# Register.net
KiCad netlist of a schematic drawn in Altium Designer
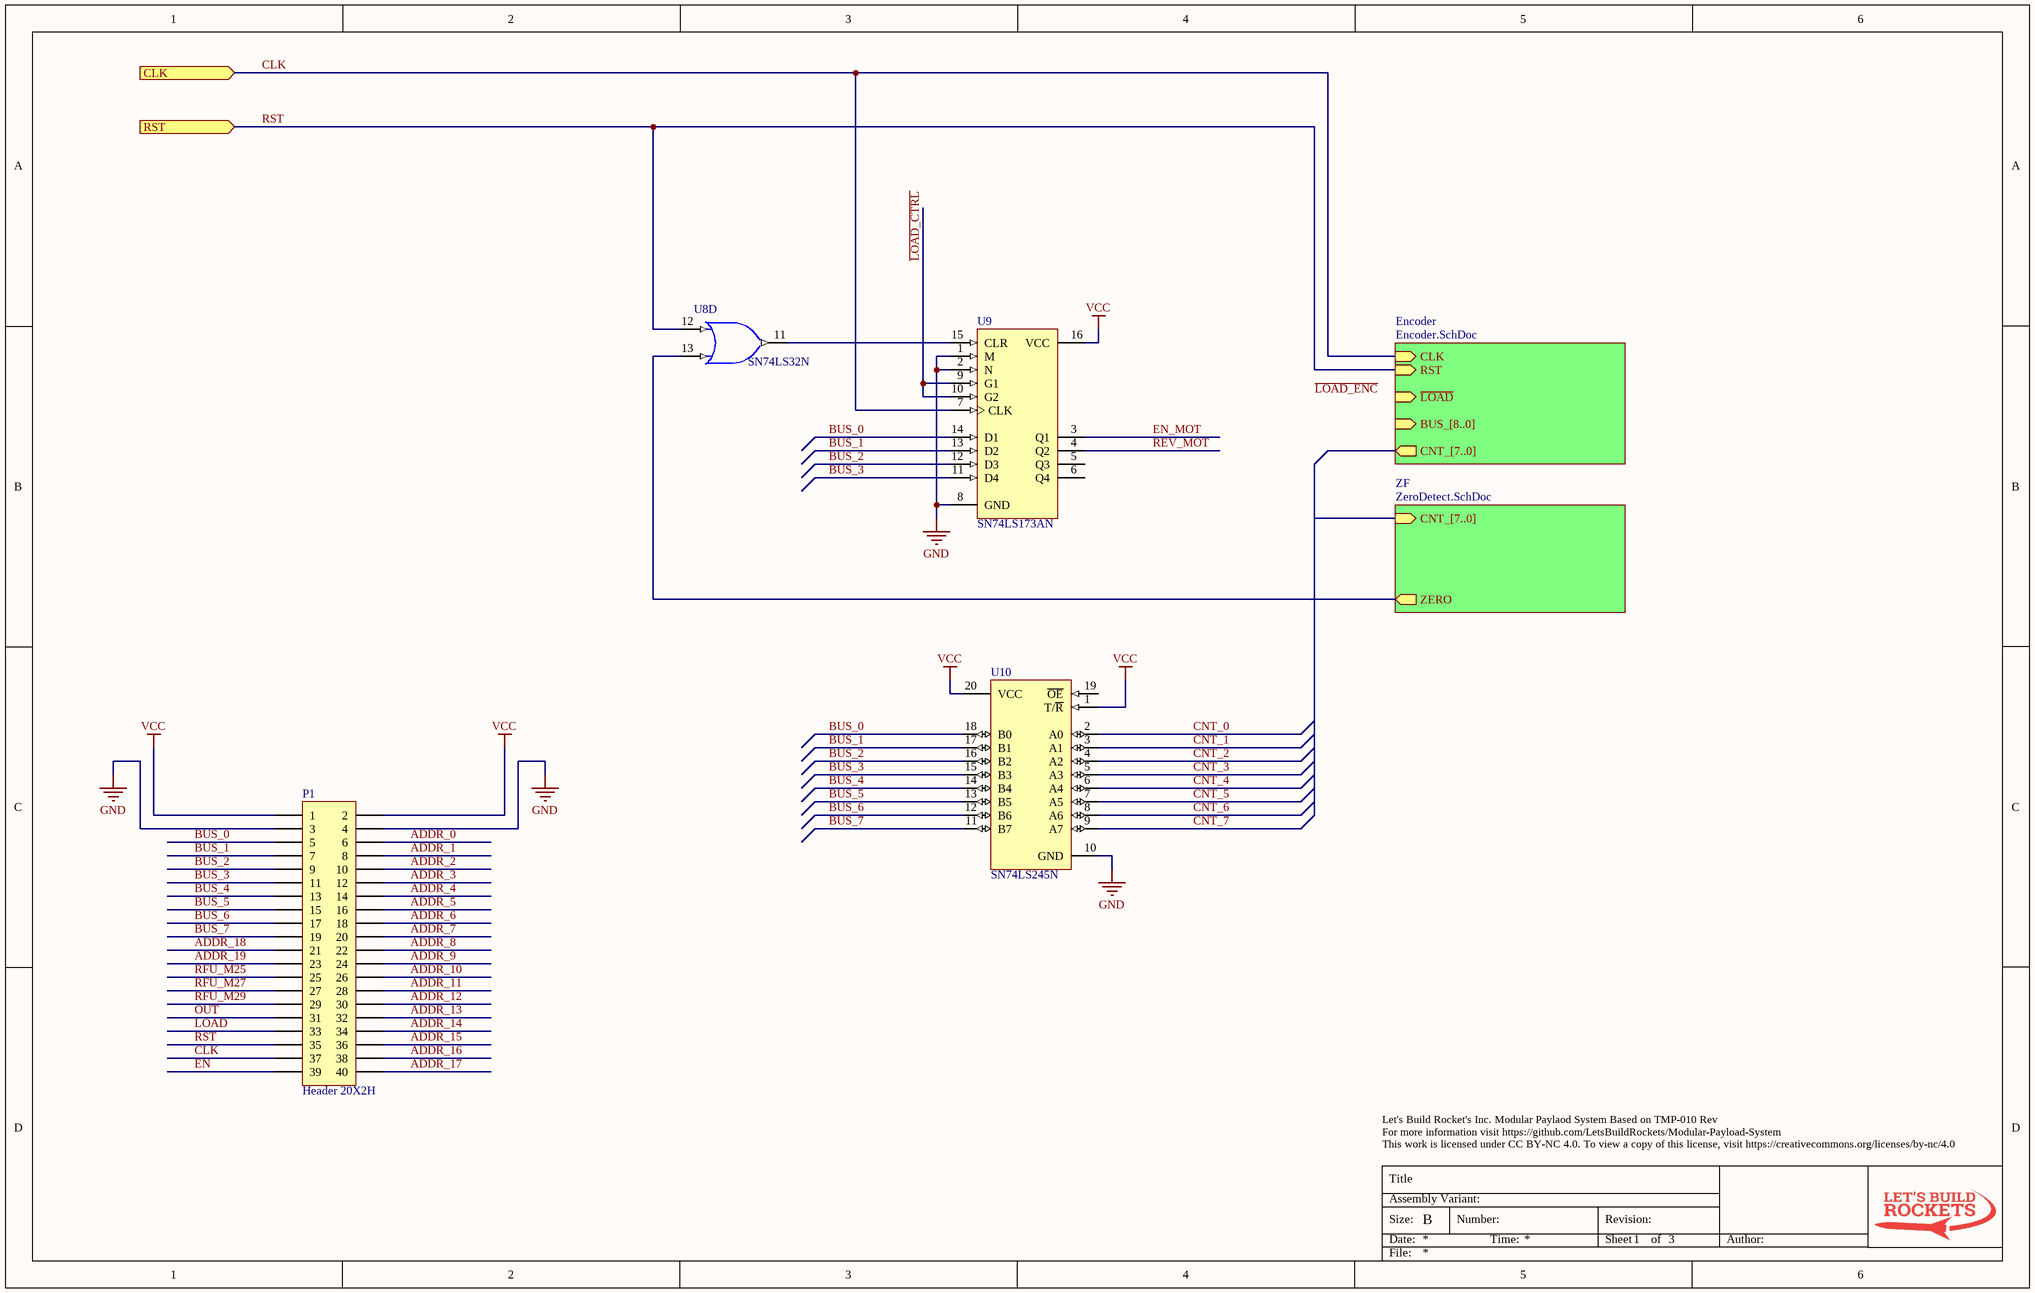
[diagram p0: Register.SchDoc]

(export (version "E")
  (design (tool "Eeschema 10.0.6"))
  (components
    (comp (ref "P1")
      (value "Header 20X2H")
      (footprint "HDR2X20H")
      (description "Header, 20-Pin, Dual row, Right Angle")
      (fields (field (name "PUBLISHER") "Altium Limited"))
      (libsource (lib "Miscellaneous Connectors") (part "Header 20X2H"))
    )
    (comp (ref "U8")
      (value "SN74LS32N")
      (footprint "N014")
      (description "Quadruple 2-Input Positive-OR Gate")
      (fields (field (name "PUBLISHER") "Altium Limited"))
      (libsource (lib "TI Logic Gate 2") (part "SN74LS32N"))
    )
    (comp (ref "U9")
      (value "SN74LS173AN")
      (footprint "N016D")
      (description "4-Bit D-Type Register with 3-State Outputs")
      (fields (field (name "PUBLISHER") "Altium Limited"))
      (libsource (lib "TI Logic Flip-Flop") (part "SN74LS173AN"))
    )
    (comp (ref "U10")
      (value "SN74LS245N")
      (footprint "N020")
      (description "Octal Bus Transceiver with 3-State Outputs")
      (fields (field (name "PUBLISHER") "Altium Limited"))
      (libsource (lib "TI Interface 8-Bit Line Transceiver") (part "SN74LS245N"))
    )
  )
  (nets
    (net (code "1") (name "/ADDR_0") (class "Default")
      (node (ref "P1") (pin "6") (pinfunction "6_6") (pintype "passive"))
    )
    (net (code "2") (name "/ADDR_1") (class "Default")
      (node (ref "P1") (pin "8") (pinfunction "8_8") (pintype "passive"))
    )
    (net (code "3") (name "/ADDR_2") (class "Default")
      (node (ref "P1") (pin "10") (pinfunction "10_10") (pintype "passive"))
    )
    (net (code "4") (name "/ADDR_3") (class "Default")
      (node (ref "P1") (pin "12") (pinfunction "12_12") (pintype "passive"))
    )
    (net (code "5") (name "/ADDR_4") (class "Default")
      (node (ref "P1") (pin "14") (pinfunction "14_14") (pintype "passive"))
    )
    (net (code "6") (name "/ADDR_5") (class "Default")
      (node (ref "P1") (pin "16") (pinfunction "16_16") (pintype "passive"))
    )
    (net (code "7") (name "/ADDR_6") (class "Default")
      (node (ref "P1") (pin "18") (pinfunction "18_18") (pintype "passive"))
    )
    (net (code "8") (name "/ADDR_7") (class "Default")
      (node (ref "P1") (pin "20") (pinfunction "20_20") (pintype "passive"))
    )
    (net (code "9") (name "/ADDR_8") (class "Default")
      (node (ref "P1") (pin "22") (pinfunction "22_22") (pintype "passive"))
    )
    (net (code "10") (name "/ADDR_9") (class "Default")
      (node (ref "P1") (pin "24") (pinfunction "24_24") (pintype "passive"))
    )
    (net (code "11") (name "/ADDR_10") (class "Default")
      (node (ref "P1") (pin "26") (pinfunction "26_26") (pintype "passive"))
    )
    (net (code "12") (name "/ADDR_11") (class "Default")
      (node (ref "P1") (pin "28") (pinfunction "28_28") (pintype "passive"))
    )
    (net (code "13") (name "/ADDR_12") (class "Default")
      (node (ref "P1") (pin "30") (pinfunction "30_30") (pintype "passive"))
    )
    (net (code "14") (name "/ADDR_13") (class "Default")
      (node (ref "P1") (pin "32") (pinfunction "32_32") (pintype "passive"))
    )
    (net (code "15") (name "/ADDR_14") (class "Default")
      (node (ref "P1") (pin "34") (pinfunction "34_34") (pintype "passive"))
    )
    (net (code "16") (name "/ADDR_15") (class "Default")
      (node (ref "P1") (pin "36") (pinfunction "36_36") (pintype "passive"))
    )
    (net (code "17") (name "/ADDR_16") (class "Default")
      (node (ref "P1") (pin "38") (pinfunction "38_38") (pintype "passive"))
    )
    (net (code "18") (name "/ADDR_17") (class "Default")
      (node (ref "P1") (pin "40") (pinfunction "40_40") (pintype "passive"))
    )
    (net (code "19") (name "/ADDR_18") (class "Default")
      (node (ref "P1") (pin "21") (pinfunction "21_21") (pintype "passive"))
    )
    (net (code "20") (name "/ADDR_19") (class "Default")
      (node (ref "P1") (pin "23") (pinfunction "23_23") (pintype "passive"))
    )
    (net (code "21") (name "/BUS_0") (class "Default")
      (node (ref "P1") (pin "5") (pinfunction "5_5") (pintype "passive"))
      (node (ref "U10") (pin "18") (pinfunction "B0_18") (pintype "bidirectional"))
      (node (ref "U9") (pin "14") (pinfunction "D1_14") (pintype "input"))
    )
    (net (code "22") (name "/BUS_1") (class "Default")
      (node (ref "P1") (pin "7") (pinfunction "7_7") (pintype "passive"))
      (node (ref "U10") (pin "17") (pinfunction "B1_17") (pintype "bidirectional"))
      (node (ref "U9") (pin "13") (pinfunction "D2_13") (pintype "input"))
    )
    (net (code "23") (name "/BUS_2") (class "Default")
      (node (ref "P1") (pin "9") (pinfunction "9_9") (pintype "passive"))
      (node (ref "U10") (pin "16") (pinfunction "B2_16") (pintype "bidirectional"))
      (node (ref "U9") (pin "12") (pinfunction "D3_12") (pintype "input"))
    )
    (net (code "24") (name "/BUS_3") (class "Default")
      (node (ref "P1") (pin "11") (pinfunction "11_11") (pintype "passive"))
      (node (ref "U10") (pin "15") (pinfunction "B3_15") (pintype "bidirectional"))
      (node (ref "U9") (pin "11") (pinfunction "D4_11") (pintype "input"))
    )
    (net (code "25") (name "/BUS_4") (class "Default")
      (node (ref "P1") (pin "13") (pinfunction "13_13") (pintype "passive"))
      (node (ref "U10") (pin "14") (pinfunction "B4_14") (pintype "bidirectional"))
    )
    (net (code "26") (name "/BUS_5") (class "Default")
      (node (ref "P1") (pin "15") (pinfunction "15_15") (pintype "passive"))
      (node (ref "U10") (pin "13") (pinfunction "B5_13") (pintype "bidirectional"))
    )
    (net (code "27") (name "/BUS_6") (class "Default")
      (node (ref "P1") (pin "17") (pinfunction "17_17") (pintype "passive"))
      (node (ref "U10") (pin "12") (pinfunction "B6_12") (pintype "bidirectional"))
    )
    (net (code "28") (name "/BUS_7") (class "Default")
      (node (ref "P1") (pin "19") (pinfunction "19_19") (pintype "passive"))
      (node (ref "U10") (pin "11") (pinfunction "B7_11") (pintype "bidirectional"))
    )
    (net (code "30") (name "/CLK") (class "Default")
      (node (ref "P1") (pin "37") (pinfunction "37_37") (pintype "passive"))
      (node (ref "U9") (pin "7") (pinfunction "CLK_7") (pintype "input"))
    )
    (net (code "31") (name "/CNT_0") (class "Default")
      (node (ref "U10") (pin "2") (pinfunction "A0_2") (pintype "bidirectional"))
    )
    (net (code "32") (name "/CNT_1") (class "Default")
      (node (ref "U10") (pin "3") (pinfunction "A1_3") (pintype "bidirectional"))
    )
    (net (code "33") (name "/CNT_2") (class "Default")
      (node (ref "U10") (pin "4") (pinfunction "A2_4") (pintype "bidirectional"))
    )
    (net (code "34") (name "/CNT_3") (class "Default")
      (node (ref "U10") (pin "5") (pinfunction "A3_5") (pintype "bidirectional"))
    )
    (net (code "35") (name "/CNT_4") (class "Default")
      (node (ref "U10") (pin "6") (pinfunction "A4_6") (pintype "bidirectional"))
    )
    (net (code "36") (name "/CNT_5") (class "Default")
      (node (ref "U10") (pin "7") (pinfunction "A5_7") (pintype "bidirectional"))
    )
    (net (code "37") (name "/CNT_6") (class "Default")
      (node (ref "U10") (pin "8") (pinfunction "A6_8") (pintype "bidirectional"))
    )
    (net (code "38") (name "/CNT_7") (class "Default")
      (node (ref "U10") (pin "9") (pinfunction "A7_9") (pintype "bidirectional"))
    )
    (net (code "40") (name "/EN") (class "Default")
      (node (ref "P1") (pin "39") (pinfunction "39_39") (pintype "passive"))
    )
    (net (code "41") (name "/EN_MOT") (class "Default")
      (node (ref "U9") (pin "3") (pinfunction "Q1_3") (pintype "tri_state"))
    )
    (net (code "42") (name "/LOAD") (class "Default")
      (node (ref "P1") (pin "33") (pinfunction "33_33") (pintype "passive"))
    )
    (net (code "43") (name "/REV_MOT") (class "Default")
      (node (ref "U9") (pin "4") (pinfunction "Q2_4") (pintype "tri_state"))
    )
    (net (code "44") (name "/RFU_M25") (class "Default")
      (node (ref "P1") (pin "25") (pinfunction "25_25") (pintype "passive"))
    )
    (net (code "45") (name "/RFU_M27") (class "Default")
      (node (ref "P1") (pin "27") (pinfunction "27_27") (pintype "passive"))
    )
    (net (code "46") (name "/RFU_M29") (class "Default")
      (node (ref "P1") (pin "29") (pinfunction "29_29") (pintype "passive"))
    )
    (net (code "47") (name "/RST") (class "Default")
      (node (ref "P1") (pin "35") (pinfunction "35_35") (pintype "passive"))
      (node (ref "U8") (pin "12") (pinfunction "A_12") (pintype "input"))
    )
    (net (code "48") (name "/ZERO") (class "Default")
      (node (ref "U8") (pin "13") (pinfunction "B_13") (pintype "input"))
    )
    (net (code "49") (name "/~{LOAD_CTRL}") (class "Default")
      (node (ref "U9") (pin "10") (pinfunction "G2_10") (pintype "input"))
      (node (ref "U9") (pin "9") (pinfunction "G1_9") (pintype "input"))
    )
    (net (code "52") (name "/~{OUT}") (class "Default")
      (node (ref "P1") (pin "31") (pinfunction "31_31") (pintype "passive"))
    )
    (net (code "53") (name "GND") (class "Default")
      (node (ref "P1") (pin "3") (pinfunction "3_3") (pintype "passive"))
      (node (ref "P1") (pin "4") (pinfunction "4_4") (pintype "passive"))
      (node (ref "U10") (pin "10") (pinfunction "GND_10") (pintype "power_in"))
      (node (ref "U8") (pin "7") (pinfunction "GND_7") (pintype "power_in"))
      (node (ref "U9") (pin "1") (pinfunction "M_1") (pintype "input"))
      (node (ref "U9") (pin "2") (pinfunction "N_2") (pintype "input"))
      (node (ref "U9") (pin "8") (pinfunction "GND_8") (pintype "power_in"))
    )
    (net (code "54") (name "Net-(U8D-Y)") (class "Default")
      (node (ref "U8") (pin "11") (pinfunction "Y_11") (pintype "output"))
      (node (ref "U9") (pin "15") (pinfunction "CLR_15") (pintype "input"))
    )
    (net (code "55") (name "VCC") (class "Default")
      (node (ref "P1") (pin "1") (pinfunction "1_1") (pintype "passive"))
      (node (ref "P1") (pin "2") (pinfunction "2_2") (pintype "passive"))
      (node (ref "U10") (pin "1") (pinfunction "T/~{R}_1") (pintype "input"))
      (node (ref "U10") (pin "20") (pinfunction "VCC_20") (pintype "power_in"))
      (node (ref "U8") (pin "14") (pinfunction "VCC_14") (pintype "power_in"))
      (node (ref "U9") (pin "16") (pinfunction "VCC_16") (pintype "power_in"))
    )
    (net (code "56") (name "unconnected-(U9-Q3-Pad5)") (class "Default")
      (node (ref "U9") (pin "5") (pinfunction "Q3_5") (pintype "tri_state"))
    )
    (net (code "57") (name "unconnected-(U9-Q4-Pad6)") (class "Default")
      (node (ref "U9") (pin "6") (pinfunction "Q4_6") (pintype "tri_state"))
    )
    (net (code "58") (name "unconnected-(U10-~{OE}-Pad19)") (class "Default")
      (node (ref "U10") (pin "19") (pinfunction "~{OE}_19") (pintype "input"))
    )
  )
)
